# hello.net
KiCad netlist of a schematic drawn in EAGLE
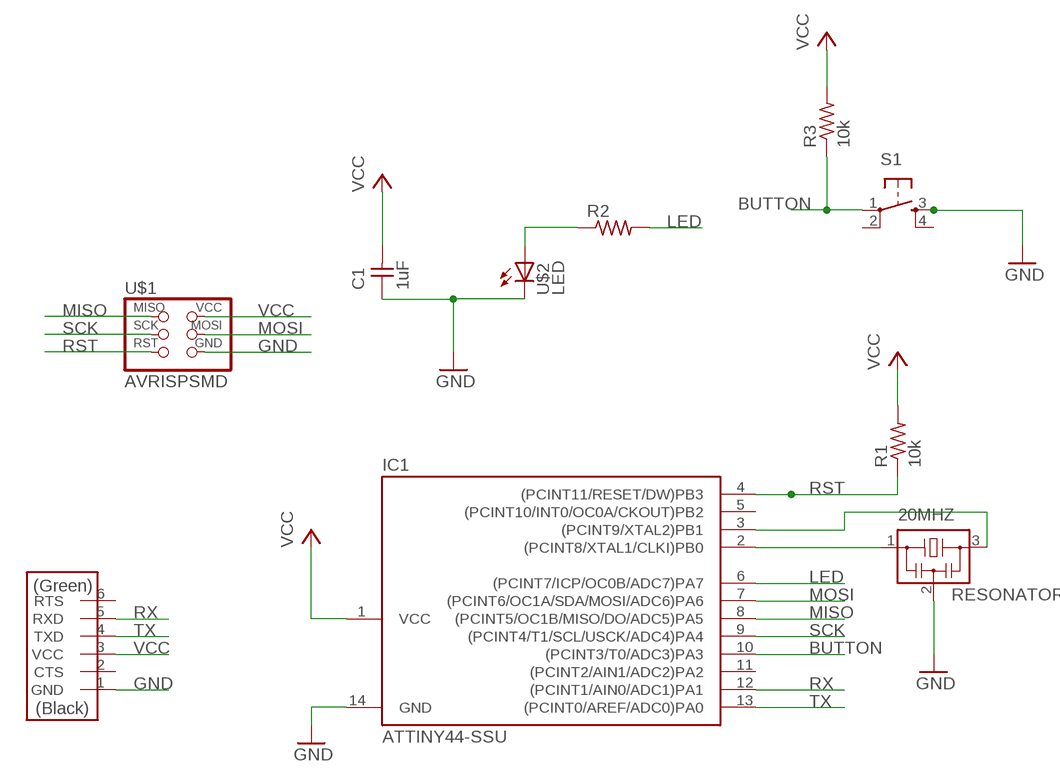
[diagram p0: schematic, sheet 1]

(export (version "E")
  (design (tool "Eeschema 10.0.6"))
  (components
    (comp (ref "20MHZ")
      (value "RESONATOR")
      (footprint "eagle-import:EFOBM")
      (libsource (lib "eagle-import") (part "RESONATOR"))
    )
    (comp (ref "C1")
      (value "1uF")
      (footprint "eagle-import:C1206")
      (libsource (lib "eagle-import") (part "CAP-UNPOLARIZED"))
    )
    (comp (ref "IC1")
      (value "ATTINY44-SSU")
      (footprint "eagle-import:SOIC14")
      (libsource (lib "eagle-import") (part "ATTINY44-SSU"))
    )
    (comp (ref "R1")
      (value "10k")
      (footprint "eagle-import:R1206")
      (libsource (lib "eagle-import") (part "RES-US1206"))
    )
    (comp (ref "R2")
      (value "RES-US1206")
      (footprint "eagle-import:R1206")
      (libsource (lib "eagle-import") (part "RES-US1206"))
    )
    (comp (ref "R3")
      (value "10k")
      (footprint "eagle-import:R1206")
      (libsource (lib "eagle-import") (part "RES-US1206"))
    )
    (comp (ref "S1")
      (value "6MM_SWITCH6MM_SWITCH")
      (footprint "eagle-import:6MM_SWITCH")
      (libsource (lib "eagle-import") (part "6MM_SWITCH6MM_SWITCH"))
    )
    (comp (ref "U$1")
      (value "AVRISPSMD")
      (footprint "eagle-import:2X03SMD")
      (libsource (lib "eagle-import") (part "AVRISPSMD"))
    )
    (comp (ref "U$2")
      (value "LED")
      (footprint "eagle-import:LED1206")
      (libsource (lib "eagle-import") (part "LED"))
    )
    (comp (ref "U$4")
      (value "FTDI-SMD-HEADER")
      (footprint "eagle-import:1X06SMD")
      (libsource (lib "eagle-import") (part "FTDI-SMD-HEADER"))
    )
  )
  (nets
    (net (code "1") (name "/BUTTON") (class "Default")
      (node (ref "IC1") (pin "10") (pinfunction "(PCINT3/T0/ADC3)PA3_10") (pintype "bidirectional"))
      (node (ref "R3") (pin "1") (pinfunction "1_1") (pintype "passive"))
      (node (ref "S1") (pin "1") (pinfunction "P_1") (pintype "passive"))
    )
    (net (code "2") (name "/LED") (class "Default")
      (node (ref "IC1") (pin "6") (pinfunction "(PCINT7/ICP/OC0B/ADC7)PA7_6") (pintype "bidirectional"))
      (node (ref "R2") (pin "2") (pinfunction "2_2") (pintype "passive"))
    )
    (net (code "3") (name "/MISO") (class "Default")
      (node (ref "IC1") (pin "8") (pinfunction "(PCINT5/OC1B/MISO/DO/ADC5)PA5_8") (pintype "bidirectional"))
      (node (ref "U$1") (pin "1") (pinfunction "MISO_1") (pintype "passive"))
    )
    (net (code "4") (name "/MOSI") (class "Default")
      (node (ref "IC1") (pin "7") (pinfunction "(PCINT6/OC1A/SDA/MOSI/ADC6)PA6_7") (pintype "bidirectional"))
      (node (ref "U$1") (pin "4") (pinfunction "MOSI_4") (pintype "passive"))
    )
    (net (code "5") (name "/RST") (class "Default")
      (node (ref "IC1") (pin "4") (pinfunction "(PCINT11/RESET/DW)PB3_4") (pintype "bidirectional"))
      (node (ref "R1") (pin "1") (pinfunction "1_1") (pintype "passive"))
      (node (ref "U$1") (pin "5") (pinfunction "RST_5") (pintype "passive"))
    )
    (net (code "6") (name "/RX") (class "Default")
      (node (ref "IC1") (pin "12") (pinfunction "(PCINT1/AIN0/ADC1)PA1_12") (pintype "bidirectional"))
      (node (ref "U$4") (pin "5") (pinfunction "RXD_5") (pintype "bidirectional"))
    )
    (net (code "7") (name "/SCK") (class "Default")
      (node (ref "IC1") (pin "9") (pinfunction "(PCINT4/T1/SCL/USCK/ADC4)PA4_9") (pintype "bidirectional"))
      (node (ref "U$1") (pin "3") (pinfunction "SCK_3") (pintype "passive"))
    )
    (net (code "8") (name "/TX") (class "Default")
      (node (ref "IC1") (pin "13") (pinfunction "(PCINT0/AREF/ADC0)PA0_13") (pintype "bidirectional"))
      (node (ref "U$4") (pin "4") (pinfunction "TXD_4") (pintype "bidirectional"))
    )
    (net (code "9") (name "GND") (class "Default")
      (node (ref "20MHZ") (pin "2") (pinfunction "2_2") (pintype "passive"))
      (node (ref "C1") (pin "1") (pinfunction "1_1") (pintype "passive"))
      (node (ref "IC1") (pin "14") (pinfunction "GND_14") (pintype "power_in"))
      (node (ref "S1") (pin "3") (pinfunction "S_3") (pintype "passive"))
      (node (ref "U$1") (pin "6") (pinfunction "GND_6") (pintype "passive"))
      (node (ref "U$2") (pin "2") (pinfunction "C_2") (pintype "passive"))
      (node (ref "U$4") (pin "1") (pinfunction "GND_1") (pintype "bidirectional"))
    )
    (net (code "10") (name "Net-(IC1-(PCINT8{slash}XTAL1{slash}CLKI)PB0)") (class "Default")
      (node (ref "20MHZ") (pin "1") (pinfunction "1_1") (pintype "passive"))
      (node (ref "IC1") (pin "2") (pinfunction "(PCINT8/XTAL1/CLKI)PB0_2") (pintype "bidirectional"))
    )
    (net (code "11") (name "Net-(IC1-(PCINT9{slash}XTAL2)PB1)") (class "Default")
      (node (ref "20MHZ") (pin "3") (pinfunction "3_3") (pintype "passive"))
      (node (ref "IC1") (pin "3") (pinfunction "(PCINT9/XTAL2)PB1_3") (pintype "bidirectional"))
    )
    (net (code "12") (name "Net-(U$2-A)") (class "Default")
      (node (ref "R2") (pin "1") (pinfunction "1_1") (pintype "passive"))
      (node (ref "U$2") (pin "1") (pinfunction "A_1") (pintype "passive"))
    )
    (net (code "13") (name "VCC") (class "Default")
      (node (ref "C1") (pin "2") (pinfunction "2_2") (pintype "passive"))
      (node (ref "IC1") (pin "1") (pinfunction "VCC_1") (pintype "power_in"))
      (node (ref "R1") (pin "2") (pinfunction "2_2") (pintype "passive"))
      (node (ref "R3") (pin "2") (pinfunction "2_2") (pintype "passive"))
      (node (ref "U$1") (pin "2") (pinfunction "VCC_2") (pintype "passive"))
      (node (ref "U$4") (pin "3") (pinfunction "VCC_3") (pintype "bidirectional"))
    )
    (net (code "14") (name "unconnected-(IC1-(PCINT2{slash}AIN1{slash}ADC2)PA2-Pad11)") (class "Default")
      (node (ref "IC1") (pin "11") (pinfunction "(PCINT2/AIN1/ADC2)PA2_11") (pintype "bidirectional"))
    )
    (net (code "15") (name "unconnected-(IC1-(PCINT10{slash}INT0{slash}OC0A{slash}CKOUT)PB2-Pad5)") (class "Default")
      (node (ref "IC1") (pin "5") (pinfunction "(PCINT10/INT0/OC0A/CKOUT)PB2_5") (pintype "bidirectional"))
    )
    (net (code "16") (name "unconnected-(S1-P1-Pad2)") (class "Default")
      (node (ref "S1") (pin "2") (pinfunction "P1_2") (pintype "passive"))
    )
    (net (code "17") (name "unconnected-(S1-S1-Pad4)") (class "Default")
      (node (ref "S1") (pin "4") (pinfunction "S1_4") (pintype "passive"))
    )
    (net (code "18") (name "unconnected-(U$4-CTS-Pad2)") (class "Default")
      (node (ref "U$4") (pin "2") (pinfunction "CTS_2") (pintype "bidirectional"))
    )
    (net (code "19") (name "unconnected-(U$4-RTS-Pad6)") (class "Default")
      (node (ref "U$4") (pin "6") (pinfunction "RTS_6") (pintype "bidirectional"))
    )
  )
)
